# RPiEvmLcd.net
KiCad netlist of a schematic drawn in EAGLE
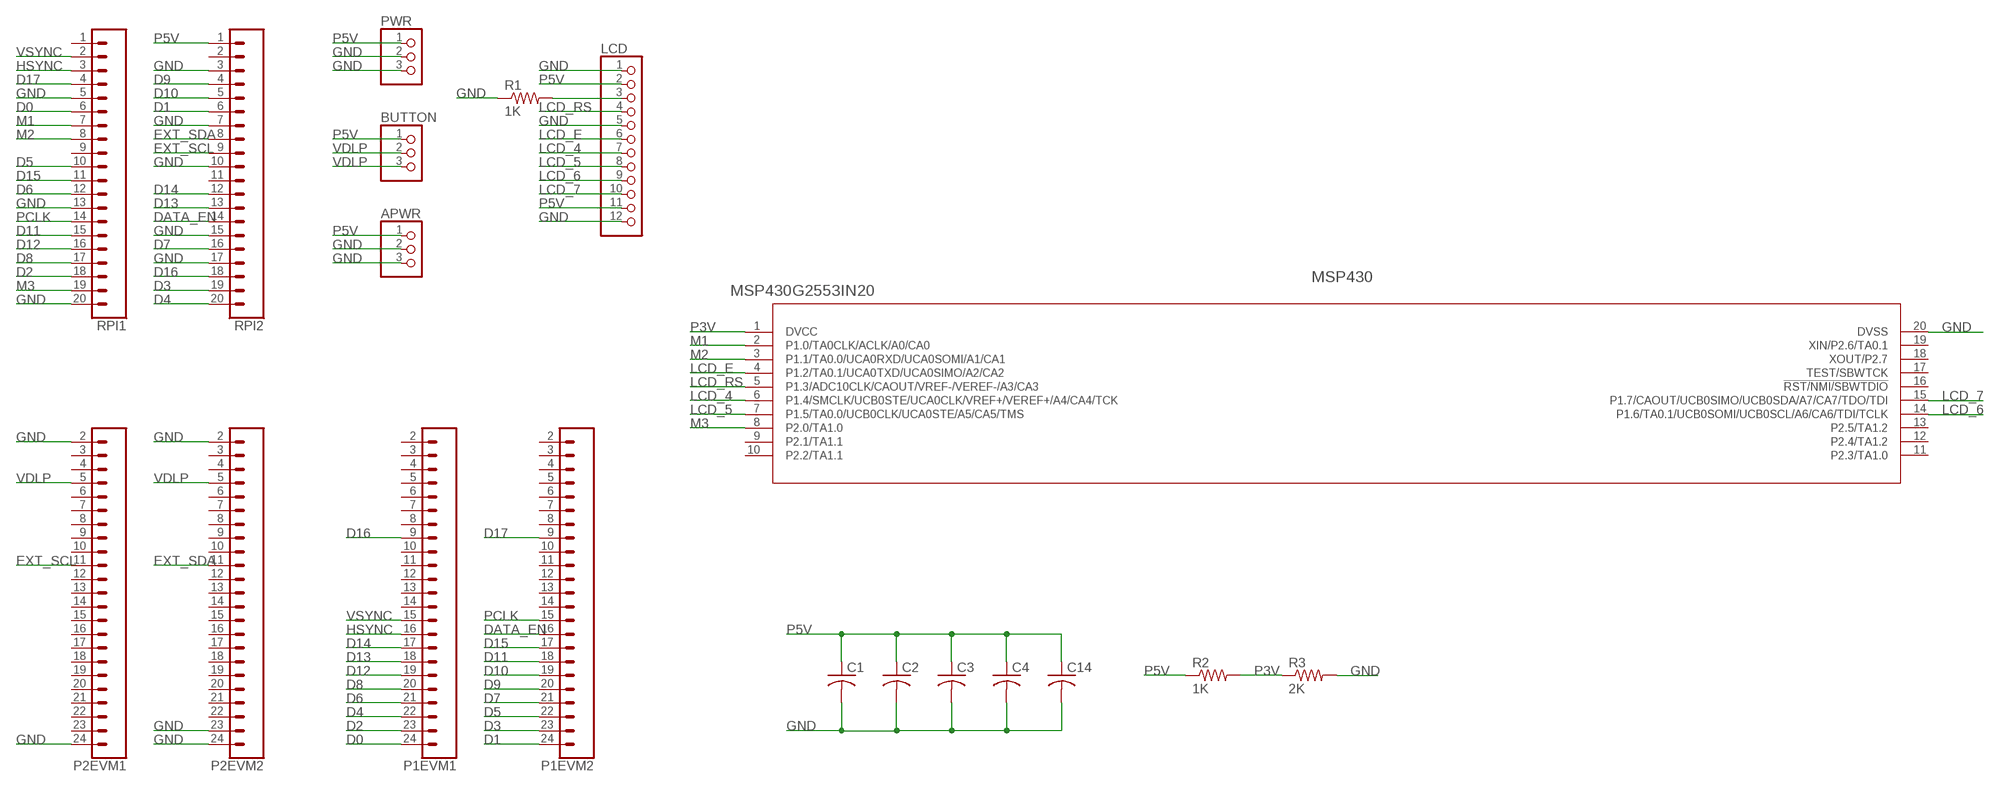
[diagram p0: schematic, sheet 1]

(export (version "E")
  (design (tool "Eeschema 10.0.6"))
  (components
    (comp (ref "APWR")
      (value "PINHD-1X3")
      (footprint "eagle-import:1X03")
      (libsource (lib "eagle-import") (part "PINHD-1X3"))
    )
    (comp (ref "BUTTON")
      (value "PINHD-1X3")
      (footprint "eagle-import:1X03")
      (libsource (lib "eagle-import") (part "PINHD-1X3"))
    )
    (comp (ref "C1")
      (value "C-US075-042X103")
      (footprint "eagle-import:C075-042X103")
      (libsource (lib "eagle-import") (part "C-US075-042X103"))
    )
    (comp (ref "C2")
      (value "C-US075-042X103")
      (footprint "eagle-import:C075-042X103")
      (libsource (lib "eagle-import") (part "C-US075-042X103"))
    )
    (comp (ref "C3")
      (value "C-US075-042X103")
      (footprint "eagle-import:C075-042X103")
      (libsource (lib "eagle-import") (part "C-US075-042X103"))
    )
    (comp (ref "C4")
      (value "C-US075-042X103")
      (footprint "eagle-import:C075-042X103")
      (libsource (lib "eagle-import") (part "C-US075-042X103"))
    )
    (comp (ref "C14")
      (value "C-US075-042X103")
      (footprint "eagle-import:C075-042X103")
      (libsource (lib "eagle-import") (part "C-US075-042X103"))
    )
    (comp (ref "LCD")
      (value "PINHD-1X12")
      (footprint "eagle-import:1X12")
      (libsource (lib "eagle-import") (part "PINHD-1X12"))
    )
    (comp (ref "MSP430")
      (value "MSP430G2553IN20")
      (footprint "eagle-import:N20_TEX")
      (libsource (lib "eagle-import") (part "MSP430G2553IN20"))
    )
    (comp (ref "P1EVM1")
      (value "CONN_23")
      (footprint "eagle-import:1X23")
      (libsource (lib "eagle-import") (part "CONN_23"))
    )
    (comp (ref "P1EVM2")
      (value "CONN_23")
      (footprint "eagle-import:1X23")
      (libsource (lib "eagle-import") (part "CONN_23"))
    )
    (comp (ref "P2EVM1")
      (value "CONN_23")
      (footprint "eagle-import:1X23")
      (libsource (lib "eagle-import") (part "CONN_23"))
    )
    (comp (ref "P2EVM2")
      (value "CONN_23")
      (footprint "eagle-import:1X23")
      (libsource (lib "eagle-import") (part "CONN_23"))
    )
    (comp (ref "PWR")
      (value "PINHD-1X3")
      (footprint "eagle-import:1X03")
      (libsource (lib "eagle-import") (part "PINHD-1X3"))
    )
    (comp (ref "R1")
      (value "1K")
      (footprint "eagle-import:0204_5")
      (libsource (lib "eagle-import") (part "R-US_0204/5"))
    )
    (comp (ref "R2")
      (value "1K")
      (footprint "eagle-import:0204_5")
      (libsource (lib "eagle-import") (part "R-US_0204/5"))
    )
    (comp (ref "R3")
      (value "2K")
      (footprint "eagle-import:0204_5")
      (libsource (lib "eagle-import") (part "R-US_0204/5"))
    )
    (comp (ref "RPI1")
      (value "CONN_20")
      (footprint "eagle-import:1X20")
      (libsource (lib "eagle-import") (part "CONN_20"))
    )
    (comp (ref "RPI2")
      (value "CONN_20")
      (footprint "eagle-import:1X20")
      (libsource (lib "eagle-import") (part "CONN_20"))
    )
  )
  (nets
    (net (code "1") (name "/D0") (class "Default")
      (node (ref "P1EVM1") (pin "24") (pinfunction "24_24") (pintype "passive"))
      (node (ref "RPI1") (pin "6") (pinfunction "6_6") (pintype "passive"))
    )
    (net (code "2") (name "/D1") (class "Default")
      (node (ref "P1EVM2") (pin "24") (pinfunction "24_24") (pintype "passive"))
      (node (ref "RPI2") (pin "6") (pinfunction "6_6") (pintype "passive"))
    )
    (net (code "3") (name "/D2") (class "Default")
      (node (ref "P1EVM1") (pin "23") (pinfunction "23_23") (pintype "passive"))
      (node (ref "RPI1") (pin "18") (pinfunction "18_18") (pintype "passive"))
    )
    (net (code "4") (name "/D3") (class "Default")
      (node (ref "P1EVM2") (pin "23") (pinfunction "23_23") (pintype "passive"))
      (node (ref "RPI2") (pin "19") (pinfunction "19_19") (pintype "passive"))
    )
    (net (code "5") (name "/D4") (class "Default")
      (node (ref "P1EVM1") (pin "22") (pinfunction "22_22") (pintype "passive"))
      (node (ref "RPI2") (pin "20") (pinfunction "20_20") (pintype "passive"))
    )
    (net (code "6") (name "/D5") (class "Default")
      (node (ref "P1EVM2") (pin "22") (pinfunction "22_22") (pintype "passive"))
      (node (ref "RPI1") (pin "10") (pinfunction "10_10") (pintype "passive"))
    )
    (net (code "7") (name "/D6") (class "Default")
      (node (ref "P1EVM1") (pin "21") (pinfunction "21_21") (pintype "passive"))
      (node (ref "RPI1") (pin "12") (pinfunction "12_12") (pintype "passive"))
    )
    (net (code "8") (name "/D7") (class "Default")
      (node (ref "P1EVM2") (pin "21") (pinfunction "21_21") (pintype "passive"))
      (node (ref "RPI2") (pin "16") (pinfunction "16_16") (pintype "passive"))
    )
    (net (code "9") (name "/D8") (class "Default")
      (node (ref "P1EVM1") (pin "20") (pinfunction "20_20") (pintype "passive"))
      (node (ref "RPI1") (pin "17") (pinfunction "17_17") (pintype "passive"))
    )
    (net (code "10") (name "/D9") (class "Default")
      (node (ref "P1EVM2") (pin "20") (pinfunction "20_20") (pintype "passive"))
      (node (ref "RPI2") (pin "4") (pinfunction "4_4") (pintype "passive"))
    )
    (net (code "11") (name "/D10") (class "Default")
      (node (ref "P1EVM2") (pin "19") (pinfunction "19_19") (pintype "passive"))
      (node (ref "RPI2") (pin "5") (pinfunction "5_5") (pintype "passive"))
    )
    (net (code "12") (name "/D11") (class "Default")
      (node (ref "P1EVM2") (pin "18") (pinfunction "18_18") (pintype "passive"))
      (node (ref "RPI1") (pin "15") (pinfunction "15_15") (pintype "passive"))
    )
    (net (code "13") (name "/D12") (class "Default")
      (node (ref "P1EVM1") (pin "19") (pinfunction "19_19") (pintype "passive"))
      (node (ref "RPI1") (pin "16") (pinfunction "16_16") (pintype "passive"))
    )
    (net (code "14") (name "/D13") (class "Default")
      (node (ref "P1EVM1") (pin "18") (pinfunction "18_18") (pintype "passive"))
      (node (ref "RPI2") (pin "13") (pinfunction "13_13") (pintype "passive"))
    )
    (net (code "15") (name "/D14") (class "Default")
      (node (ref "P1EVM1") (pin "17") (pinfunction "17_17") (pintype "passive"))
      (node (ref "RPI2") (pin "12") (pinfunction "12_12") (pintype "passive"))
    )
    (net (code "16") (name "/D15") (class "Default")
      (node (ref "P1EVM2") (pin "17") (pinfunction "17_17") (pintype "passive"))
      (node (ref "RPI1") (pin "11") (pinfunction "11_11") (pintype "passive"))
    )
    (net (code "17") (name "/D16") (class "Default")
      (node (ref "P1EVM1") (pin "9") (pinfunction "9_9") (pintype "passive"))
      (node (ref "RPI2") (pin "18") (pinfunction "18_18") (pintype "passive"))
    )
    (net (code "18") (name "/D17") (class "Default")
      (node (ref "P1EVM2") (pin "9") (pinfunction "9_9") (pintype "passive"))
      (node (ref "RPI1") (pin "4") (pinfunction "4_4") (pintype "passive"))
    )
    (net (code "19") (name "/DATA_EN") (class "Default")
      (node (ref "P1EVM2") (pin "16") (pinfunction "16_16") (pintype "passive"))
      (node (ref "RPI2") (pin "14") (pinfunction "14_14") (pintype "passive"))
    )
    (net (code "20") (name "/EXT_SCL") (class "Default")
      (node (ref "P2EVM1") (pin "11") (pinfunction "11_11") (pintype "passive"))
      (node (ref "RPI2") (pin "9") (pinfunction "9_9") (pintype "passive"))
    )
    (net (code "21") (name "/EXT_SDA") (class "Default")
      (node (ref "P2EVM2") (pin "11") (pinfunction "11_11") (pintype "passive"))
      (node (ref "RPI2") (pin "8") (pinfunction "8_8") (pintype "passive"))
    )
    (net (code "22") (name "/GND") (class "Default")
      (node (ref "APWR") (pin "2") (pinfunction "2_2") (pintype "passive"))
      (node (ref "APWR") (pin "3") (pinfunction "3_3") (pintype "passive"))
      (node (ref "C1") (pin "2") (pinfunction "2_2") (pintype "passive"))
      (node (ref "C14") (pin "2") (pinfunction "2_2") (pintype "passive"))
      (node (ref "C2") (pin "2") (pinfunction "2_2") (pintype "passive"))
      (node (ref "C3") (pin "2") (pinfunction "2_2") (pintype "passive"))
      (node (ref "C4") (pin "2") (pinfunction "2_2") (pintype "passive"))
      (node (ref "LCD") (pin "1") (pinfunction "1_1") (pintype "passive"))
      (node (ref "LCD") (pin "12") (pinfunction "12_12") (pintype "passive"))
      (node (ref "LCD") (pin "5") (pinfunction "5_5") (pintype "passive"))
      (node (ref "MSP430") (pin "20") (pinfunction "DVSS_20") (pintype "power_in"))
      (node (ref "P2EVM1") (pin "2") (pinfunction "2_2") (pintype "passive"))
      (node (ref "P2EVM1") (pin "24") (pinfunction "24_24") (pintype "passive"))
      (node (ref "P2EVM2") (pin "2") (pinfunction "2_2") (pintype "passive"))
      (node (ref "P2EVM2") (pin "23") (pinfunction "23_23") (pintype "passive"))
      (node (ref "P2EVM2") (pin "24") (pinfunction "24_24") (pintype "passive"))
      (node (ref "PWR") (pin "2") (pinfunction "2_2") (pintype "passive"))
      (node (ref "PWR") (pin "3") (pinfunction "3_3") (pintype "passive"))
      (node (ref "R1") (pin "1") (pinfunction "1_1") (pintype "passive"))
      (node (ref "R3") (pin "2") (pinfunction "2_2") (pintype "passive"))
      (node (ref "RPI1") (pin "13") (pinfunction "13_13") (pintype "passive"))
      (node (ref "RPI1") (pin "20") (pinfunction "20_20") (pintype "passive"))
      (node (ref "RPI1") (pin "5") (pinfunction "5_5") (pintype "passive"))
      (node (ref "RPI2") (pin "10") (pinfunction "10_10") (pintype "passive"))
      (node (ref "RPI2") (pin "15") (pinfunction "15_15") (pintype "passive"))
      (node (ref "RPI2") (pin "17") (pinfunction "17_17") (pintype "passive"))
      (node (ref "RPI2") (pin "3") (pinfunction "3_3") (pintype "passive"))
      (node (ref "RPI2") (pin "7") (pinfunction "7_7") (pintype "passive"))
    )
    (net (code "23") (name "/HSYNC") (class "Default")
      (node (ref "P1EVM1") (pin "16") (pinfunction "16_16") (pintype "passive"))
      (node (ref "RPI1") (pin "3") (pinfunction "3_3") (pintype "passive"))
    )
    (net (code "24") (name "/LCD_4") (class "Default")
      (node (ref "LCD") (pin "7") (pinfunction "7_7") (pintype "passive"))
      (node (ref "MSP430") (pin "6") (pinfunction "P1.4/SMCLK/UCB0STE/UCA0CLK/VREF+/VEREF+/A4/CA4/TCK_6") (pintype "bidirectional"))
    )
    (net (code "25") (name "/LCD_5") (class "Default")
      (node (ref "LCD") (pin "8") (pinfunction "8_8") (pintype "passive"))
      (node (ref "MSP430") (pin "7") (pinfunction "P1.5/TA0.0/UCB0CLK/UCA0STE/A5/CA5/TMS_7") (pintype "bidirectional"))
    )
    (net (code "26") (name "/LCD_6") (class "Default")
      (node (ref "LCD") (pin "9") (pinfunction "9_9") (pintype "passive"))
      (node (ref "MSP430") (pin "14") (pinfunction "P1.6/TA0.1/UCB0SOMI/UCB0SCL/A6/CA6/TDI/TCLK_14") (pintype "bidirectional"))
    )
    (net (code "27") (name "/LCD_7") (class "Default")
      (node (ref "LCD") (pin "10") (pinfunction "10_10") (pintype "passive"))
      (node (ref "MSP430") (pin "15") (pinfunction "P1.7/CAOUT/UCB0SIMO/UCB0SDA/A7/CA7/TDO/TDI_15") (pintype "bidirectional"))
    )
    (net (code "28") (name "/LCD_E") (class "Default")
      (node (ref "LCD") (pin "6") (pinfunction "6_6") (pintype "passive"))
      (node (ref "MSP430") (pin "4") (pinfunction "P1.2/TA0.1/UCA0TXD/UCA0SIMO/A2/CA2_4") (pintype "bidirectional"))
    )
    (net (code "29") (name "/LCD_RS") (class "Default")
      (node (ref "LCD") (pin "4") (pinfunction "4_4") (pintype "passive"))
      (node (ref "MSP430") (pin "5") (pinfunction "P1.3/ADC10CLK/CAOUT/VREF-/VEREF-/A3/CA3_5") (pintype "bidirectional"))
    )
    (net (code "30") (name "/M1") (class "Default")
      (node (ref "MSP430") (pin "2") (pinfunction "P1.0/TA0CLK/ACLK/A0/CA0_2") (pintype "bidirectional"))
      (node (ref "RPI1") (pin "7") (pinfunction "7_7") (pintype "passive"))
    )
    (net (code "31") (name "/M2") (class "Default")
      (node (ref "MSP430") (pin "3") (pinfunction "P1.1/TA0.0/UCA0RXD/UCA0SOMI/A1/CA1_3") (pintype "bidirectional"))
      (node (ref "RPI1") (pin "8") (pinfunction "8_8") (pintype "passive"))
    )
    (net (code "32") (name "/M3") (class "Default")
      (node (ref "MSP430") (pin "8") (pinfunction "P2.0/TA1.0_8") (pintype "bidirectional"))
      (node (ref "RPI1") (pin "19") (pinfunction "19_19") (pintype "passive"))
    )
    (net (code "33") (name "/P3V") (class "Default")
      (node (ref "MSP430") (pin "1") (pinfunction "DVCC_1") (pintype "power_in"))
      (node (ref "R2") (pin "2") (pinfunction "2_2") (pintype "passive"))
      (node (ref "R3") (pin "1") (pinfunction "1_1") (pintype "passive"))
    )
    (net (code "34") (name "/P5V") (class "Default")
      (node (ref "APWR") (pin "1") (pinfunction "1_1") (pintype "passive"))
      (node (ref "BUTTON") (pin "1") (pinfunction "1_1") (pintype "passive"))
      (node (ref "C1") (pin "1") (pinfunction "1_1") (pintype "passive"))
      (node (ref "C14") (pin "1") (pinfunction "1_1") (pintype "passive"))
      (node (ref "C2") (pin "1") (pinfunction "1_1") (pintype "passive"))
      (node (ref "C3") (pin "1") (pinfunction "1_1") (pintype "passive"))
      (node (ref "C4") (pin "1") (pinfunction "1_1") (pintype "passive"))
      (node (ref "LCD") (pin "11") (pinfunction "11_11") (pintype "passive"))
      (node (ref "LCD") (pin "2") (pinfunction "2_2") (pintype "passive"))
      (node (ref "PWR") (pin "1") (pinfunction "1_1") (pintype "passive"))
      (node (ref "R2") (pin "1") (pinfunction "1_1") (pintype "passive"))
      (node (ref "RPI2") (pin "1") (pinfunction "1_1") (pintype "passive"))
    )
    (net (code "35") (name "/PCLK") (class "Default")
      (node (ref "P1EVM2") (pin "15") (pinfunction "15_15") (pintype "passive"))
      (node (ref "RPI1") (pin "14") (pinfunction "14_14") (pintype "passive"))
    )
    (net (code "36") (name "/VDLP") (class "Default")
      (node (ref "BUTTON") (pin "2") (pinfunction "2_2") (pintype "passive"))
      (node (ref "BUTTON") (pin "3") (pinfunction "3_3") (pintype "passive"))
      (node (ref "P2EVM1") (pin "5") (pinfunction "5_5") (pintype "passive"))
      (node (ref "P2EVM2") (pin "5") (pinfunction "5_5") (pintype "passive"))
    )
    (net (code "37") (name "/VSYNC") (class "Default")
      (node (ref "P1EVM1") (pin "15") (pinfunction "15_15") (pintype "passive"))
      (node (ref "RPI1") (pin "2") (pinfunction "2_2") (pintype "passive"))
    )
    (net (code "38") (name "Net-(LCD-Pad3)") (class "Default")
      (node (ref "LCD") (pin "3") (pinfunction "3_3") (pintype "passive"))
      (node (ref "R1") (pin "2") (pinfunction "2_2") (pintype "passive"))
    )
    (net (code "39") (name "unconnected-(MSP430-P2.1{slash}TA1.1-Pad9)") (class "Default")
      (node (ref "MSP430") (pin "9") (pinfunction "P2.1/TA1.1_9") (pintype "bidirectional"))
    )
    (net (code "40") (name "unconnected-(MSP430-P2.2{slash}TA1.1-Pad10)") (class "Default")
      (node (ref "MSP430") (pin "10") (pinfunction "P2.2/TA1.1_10") (pintype "bidirectional"))
    )
    (net (code "41") (name "unconnected-(MSP430-P2.3{slash}TA1.0-Pad11)") (class "Default")
      (node (ref "MSP430") (pin "11") (pinfunction "P2.3/TA1.0_11") (pintype "bidirectional"))
    )
    (net (code "42") (name "unconnected-(MSP430-P2.4{slash}TA1.2-Pad12)") (class "Default")
      (node (ref "MSP430") (pin "12") (pinfunction "P2.4/TA1.2_12") (pintype "bidirectional"))
    )
    (net (code "43") (name "unconnected-(MSP430-P2.5{slash}TA1.2-Pad13)") (class "Default")
      (node (ref "MSP430") (pin "13") (pinfunction "P2.5/TA1.2_13") (pintype "bidirectional"))
    )
    (net (code "44") (name "unconnected-(MSP430-TEST{slash}SBWTCK-Pad17)") (class "Default")
      (node (ref "MSP430") (pin "17") (pinfunction "TEST/SBWTCK_17") (pintype "bidirectional"))
    )
    (net (code "45") (name "unconnected-(MSP430-XIN{slash}P2.6{slash}TA0.1-Pad19)") (class "Default")
      (node (ref "MSP430") (pin "19") (pinfunction "XIN/P2.6/TA0.1_19") (pintype "bidirectional"))
    )
    (net (code "46") (name "unconnected-(MSP430-XOUT{slash}P2.7-Pad18)") (class "Default")
      (node (ref "MSP430") (pin "18") (pinfunction "XOUT/P2.7_18") (pintype "bidirectional"))
    )
    (net (code "47") (name "unconnected-(MSP430-~{RST{slash}NMI{slash}SBWTDIO}-Pad16)") (class "Default")
      (node (ref "MSP430") (pin "16") (pinfunction "~{RST/NMI/SBWTDIO}_16") (pintype "bidirectional"))
    )
    (net (code "48") (name "unconnected-(P1EVM1-Pad2)") (class "Default")
      (node (ref "P1EVM1") (pin "2") (pinfunction "2_2") (pintype "passive"))
    )
    (net (code "49") (name "unconnected-(P1EVM1-Pad3)") (class "Default")
      (node (ref "P1EVM1") (pin "3") (pinfunction "3_3") (pintype "passive"))
    )
    (net (code "50") (name "unconnected-(P1EVM1-Pad4)") (class "Default")
      (node (ref "P1EVM1") (pin "4") (pinfunction "4_4") (pintype "passive"))
    )
    (net (code "51") (name "unconnected-(P1EVM1-Pad5)") (class "Default")
      (node (ref "P1EVM1") (pin "5") (pinfunction "5_5") (pintype "passive"))
    )
    (net (code "52") (name "unconnected-(P1EVM1-Pad6)") (class "Default")
      (node (ref "P1EVM1") (pin "6") (pinfunction "6_6") (pintype "passive"))
    )
    (net (code "53") (name "unconnected-(P1EVM1-Pad7)") (class "Default")
      (node (ref "P1EVM1") (pin "7") (pinfunction "7_7") (pintype "passive"))
    )
    (net (code "54") (name "unconnected-(P1EVM1-Pad8)") (class "Default")
      (node (ref "P1EVM1") (pin "8") (pinfunction "8_8") (pintype "passive"))
    )
    (net (code "55") (name "unconnected-(P1EVM1-Pad10)") (class "Default")
      (node (ref "P1EVM1") (pin "10") (pinfunction "10_10") (pintype "passive"))
    )
    (net (code "56") (name "unconnected-(P1EVM1-Pad11)") (class "Default")
      (node (ref "P1EVM1") (pin "11") (pinfunction "11_11") (pintype "passive"))
    )
    (net (code "57") (name "unconnected-(P1EVM1-Pad12)") (class "Default")
      (node (ref "P1EVM1") (pin "12") (pinfunction "12_12") (pintype "passive"))
    )
    (net (code "58") (name "unconnected-(P1EVM1-Pad13)") (class "Default")
      (node (ref "P1EVM1") (pin "13") (pinfunction "13_13") (pintype "passive"))
    )
    (net (code "59") (name "unconnected-(P1EVM1-Pad14)") (class "Default")
      (node (ref "P1EVM1") (pin "14") (pinfunction "14_14") (pintype "passive"))
    )
    (net (code "60") (name "unconnected-(P1EVM2-Pad2)") (class "Default")
      (node (ref "P1EVM2") (pin "2") (pinfunction "2_2") (pintype "passive"))
    )
    (net (code "61") (name "unconnected-(P1EVM2-Pad3)") (class "Default")
      (node (ref "P1EVM2") (pin "3") (pinfunction "3_3") (pintype "passive"))
    )
    (net (code "62") (name "unconnected-(P1EVM2-Pad4)") (class "Default")
      (node (ref "P1EVM2") (pin "4") (pinfunction "4_4") (pintype "passive"))
    )
    (net (code "63") (name "unconnected-(P1EVM2-Pad5)") (class "Default")
      (node (ref "P1EVM2") (pin "5") (pinfunction "5_5") (pintype "passive"))
    )
    (net (code "64") (name "unconnected-(P1EVM2-Pad6)") (class "Default")
      (node (ref "P1EVM2") (pin "6") (pinfunction "6_6") (pintype "passive"))
    )
    (net (code "65") (name "unconnected-(P1EVM2-Pad7)") (class "Default")
      (node (ref "P1EVM2") (pin "7") (pinfunction "7_7") (pintype "passive"))
    )
    (net (code "66") (name "unconnected-(P1EVM2-Pad8)") (class "Default")
      (node (ref "P1EVM2") (pin "8") (pinfunction "8_8") (pintype "passive"))
    )
    (net (code "67") (name "unconnected-(P1EVM2-Pad10)") (class "Default")
      (node (ref "P1EVM2") (pin "10") (pinfunction "10_10") (pintype "passive"))
    )
    (net (code "68") (name "unconnected-(P1EVM2-Pad11)") (class "Default")
      (node (ref "P1EVM2") (pin "11") (pinfunction "11_11") (pintype "passive"))
    )
    (net (code "69") (name "unconnected-(P1EVM2-Pad12)") (class "Default")
      (node (ref "P1EVM2") (pin "12") (pinfunction "12_12") (pintype "passive"))
    )
    (net (code "70") (name "unconnected-(P1EVM2-Pad13)") (class "Default")
      (node (ref "P1EVM2") (pin "13") (pinfunction "13_13") (pintype "passive"))
    )
    (net (code "71") (name "unconnected-(P1EVM2-Pad14)") (class "Default")
      (node (ref "P1EVM2") (pin "14") (pinfunction "14_14") (pintype "passive"))
    )
    (net (code "72") (name "unconnected-(P2EVM1-Pad3)") (class "Default")
      (node (ref "P2EVM1") (pin "3") (pinfunction "3_3") (pintype "passive"))
    )
    (net (code "73") (name "unconnected-(P2EVM1-Pad4)") (class "Default")
      (node (ref "P2EVM1") (pin "4") (pinfunction "4_4") (pintype "passive"))
    )
    (net (code "74") (name "unconnected-(P2EVM1-Pad6)") (class "Default")
      (node (ref "P2EVM1") (pin "6") (pinfunction "6_6") (pintype "passive"))
    )
    (net (code "75") (name "unconnected-(P2EVM1-Pad7)") (class "Default")
      (node (ref "P2EVM1") (pin "7") (pinfunction "7_7") (pintype "passive"))
    )
    (net (code "76") (name "unconnected-(P2EVM1-Pad8)") (class "Default")
      (node (ref "P2EVM1") (pin "8") (pinfunction "8_8") (pintype "passive"))
    )
    (net (code "77") (name "unconnected-(P2EVM1-Pad9)") (class "Default")
      (node (ref "P2EVM1") (pin "9") (pinfunction "9_9") (pintype "passive"))
    )
    (net (code "78") (name "unconnected-(P2EVM1-Pad10)") (class "Default")
      (node (ref "P2EVM1") (pin "10") (pinfunction "10_10") (pintype "passive"))
    )
    (net (code "79") (name "unconnected-(P2EVM1-Pad12)") (class "Default")
      (node (ref "P2EVM1") (pin "12") (pinfunction "12_12") (pintype "passive"))
    )
    (net (code "80") (name "unconnected-(P2EVM1-Pad13)") (class "Default")
      (node (ref "P2EVM1") (pin "13") (pinfunction "13_13") (pintype "passive"))
    )
    (net (code "81") (name "unconnected-(P2EVM1-Pad14)") (class "Default")
      (node (ref "P2EVM1") (pin "14") (pinfunction "14_14") (pintype "passive"))
    )
    (net (code "82") (name "unconnected-(P2EVM1-Pad15)") (class "Default")
      (node (ref "P2EVM1") (pin "15") (pinfunction "15_15") (pintype "passive"))
    )
    (net (code "83") (name "unconnected-(P2EVM1-Pad16)") (class "Default")
      (node (ref "P2EVM1") (pin "16") (pinfunction "16_16") (pintype "passive"))
    )
    (net (code "84") (name "unconnected-(P2EVM1-Pad17)") (class "Default")
      (node (ref "P2EVM1") (pin "17") (pinfunction "17_17") (pintype "passive"))
    )
    (net (code "85") (name "unconnected-(P2EVM1-Pad18)") (class "Default")
      (node (ref "P2EVM1") (pin "18") (pinfunction "18_18") (pintype "passive"))
    )
    (net (code "86") (name "unconnected-(P2EVM1-Pad19)") (class "Default")
      (node (ref "P2EVM1") (pin "19") (pinfunction "19_19") (pintype "passive"))
    )
    (net (code "87") (name "unconnected-(P2EVM1-Pad20)") (class "Default")
      (node (ref "P2EVM1") (pin "20") (pinfunction "20_20") (pintype "passive"))
    )
    (net (code "88") (name "unconnected-(P2EVM1-Pad21)") (class "Default")
      (node (ref "P2EVM1") (pin "21") (pinfunction "21_21") (pintype "passive"))
    )
    (net (code "89") (name "unconnected-(P2EVM1-Pad22)") (class "Default")
      (node (ref "P2EVM1") (pin "22") (pinfunction "22_22") (pintype "passive"))
    )
    (net (code "90") (name "unconnected-(P2EVM1-Pad23)") (class "Default")
      (node (ref "P2EVM1") (pin "23") (pinfunction "23_23") (pintype "passive"))
    )
    (net (code "91") (name "unconnected-(P2EVM2-Pad3)") (class "Default")
      (node (ref "P2EVM2") (pin "3") (pinfunction "3_3") (pintype "passive"))
    )
    (net (code "92") (name "unconnected-(P2EVM2-Pad4)") (class "Default")
      (node (ref "P2EVM2") (pin "4") (pinfunction "4_4") (pintype "passive"))
    )
    (net (code "93") (name "unconnected-(P2EVM2-Pad6)") (class "Default")
      (node (ref "P2EVM2") (pin "6") (pinfunction "6_6") (pintype "passive"))
    )
    (net (code "94") (name "unconnected-(P2EVM2-Pad7)") (class "Default")
      (node (ref "P2EVM2") (pin "7") (pinfunction "7_7") (pintype "passive"))
    )
    (net (code "95") (name "unconnected-(P2EVM2-Pad8)") (class "Default")
      (node (ref "P2EVM2") (pin "8") (pinfunction "8_8") (pintype "passive"))
    )
    (net (code "96") (name "unconnected-(P2EVM2-Pad9)") (class "Default")
      (node (ref "P2EVM2") (pin "9") (pinfunction "9_9") (pintype "passive"))
    )
    (net (code "97") (name "unconnected-(P2EVM2-Pad10)") (class "Default")
      (node (ref "P2EVM2") (pin "10") (pinfunction "10_10") (pintype "passive"))
    )
    (net (code "98") (name "unconnected-(P2EVM2-Pad12)") (class "Default")
      (node (ref "P2EVM2") (pin "12") (pinfunction "12_12") (pintype "passive"))
    )
    (net (code "99") (name "unconnected-(P2EVM2-Pad13)") (class "Default")
      (node (ref "P2EVM2") (pin "13") (pinfunction "13_13") (pintype "passive"))
    )
    (net (code "100") (name "unconnected-(P2EVM2-Pad14)") (class "Default")
      (node (ref "P2EVM2") (pin "14") (pinfunction "14_14") (pintype "passive"))
    )
    (net (code "101") (name "unconnected-(P2EVM2-Pad15)") (class "Default")
      (node (ref "P2EVM2") (pin "15") (pinfunction "15_15") (pintype "passive"))
    )
    (net (code "102") (name "unconnected-(P2EVM2-Pad16)") (class "Default")
      (node (ref "P2EVM2") (pin "16") (pinfunction "16_16") (pintype "passive"))
    )
    (net (code "103") (name "unconnected-(P2EVM2-Pad17)") (class "Default")
      (node (ref "P2EVM2") (pin "17") (pinfunction "17_17") (pintype "passive"))
    )
    (net (code "104") (name "unconnected-(P2EVM2-Pad18)") (class "Default")
      (node (ref "P2EVM2") (pin "18") (pinfunction "18_18") (pintype "passive"))
    )
    (net (code "105") (name "unconnected-(P2EVM2-Pad19)") (class "Default")
      (node (ref "P2EVM2") (pin "19") (pinfunction "19_19") (pintype "passive"))
    )
    (net (code "106") (name "unconnected-(P2EVM2-Pad20)") (class "Default")
      (node (ref "P2EVM2") (pin "20") (pinfunction "20_20") (pintype "passive"))
    )
    (net (code "107") (name "unconnected-(P2EVM2-Pad21)") (class "Default")
      (node (ref "P2EVM2") (pin "21") (pinfunction "21_21") (pintype "passive"))
    )
    (net (code "108") (name "unconnected-(P2EVM2-Pad22)") (class "Default")
      (node (ref "P2EVM2") (pin "22") (pinfunction "22_22") (pintype "passive"))
    )
    (net (code "109") (name "unconnected-(RPI1-Pad1)") (class "Default")
      (node (ref "RPI1") (pin "1") (pinfunction "1_1") (pintype "passive"))
    )
    (net (code "110") (name "unconnected-(RPI1-Pad9)") (class "Default")
      (node (ref "RPI1") (pin "9") (pinfunction "9_9") (pintype "passive"))
    )
    (net (code "111") (name "unconnected-(RPI2-Pad2)") (class "Default")
      (node (ref "RPI2") (pin "2") (pinfunction "2_2") (pintype "passive"))
    )
    (net (code "112") (name "unconnected-(RPI2-Pad11)") (class "Default")
      (node (ref "RPI2") (pin "11") (pinfunction "11_11") (pintype "passive"))
    )
  )
)
